# STM32_Temperature_Control.net
KiCad netlist of a schematic drawn in EasyEDA Pro
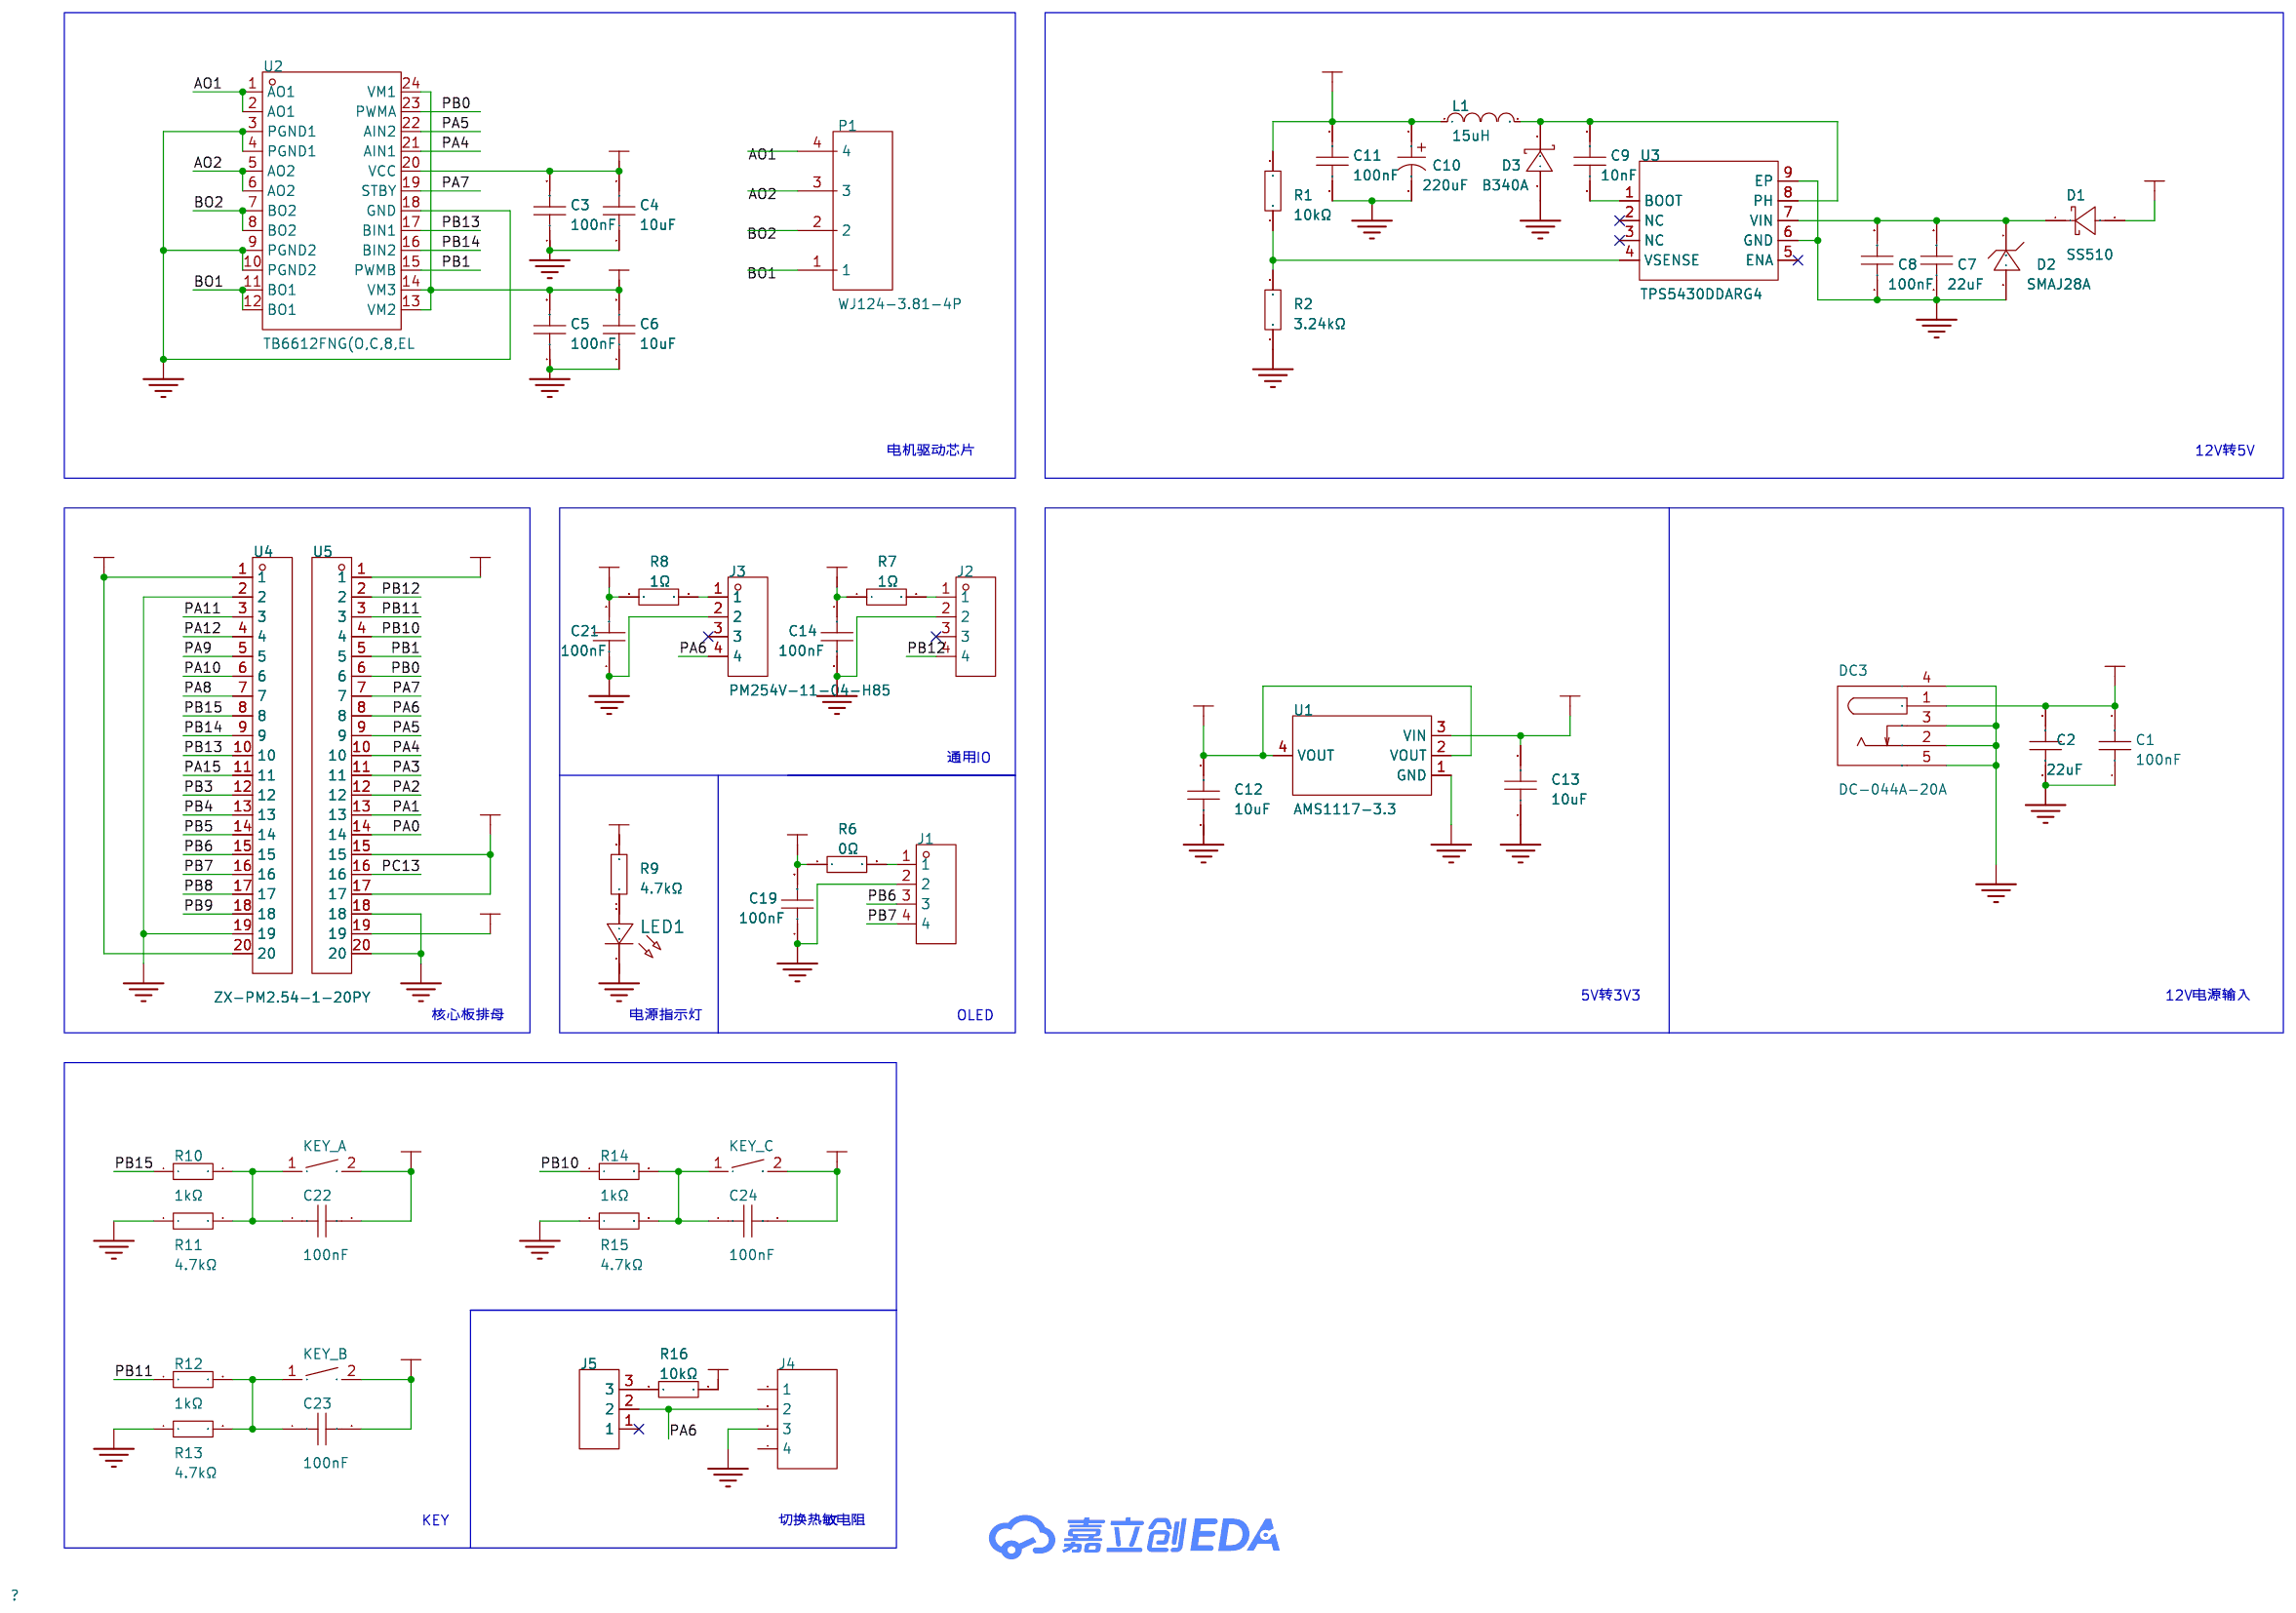
[diagram p0: schematic sheet]

(export (version "E")
  (design (tool "Eeschema 10.0.6"))
  (components
    (comp (ref "C1")
      (value "100nF")
      (footprint "easyedapro:C0603")
      (libsource (lib "easyedapro") (part "Capacitance"))
    )
    (comp (ref "C2")
      (value "22uF")
      (footprint "easyedapro:C0603")
      (fields
        (field (name "Manufacturer Part") "CL21A226MAQNNNE")
        (field (name "Manufacturer") "SAMSUNG(三星)")
      )
      (libsource (lib "easyedapro") (part "Capacitance"))
    )
    (comp (ref "C3")
      (value "100nF")
      (footprint "easyedapro:C0603")
      (libsource (lib "easyedapro") (part "Capacitance"))
    )
    (comp (ref "C4")
      (value "10uF")
      (footprint "easyedapro:C0805")
      (description "容值:10uF;精度:±10%;额定电压:50V;温度系数:X5R;")
      (fields
        (field (name "Manufacturer Part") "GRM21BR61H106KE43L")
        (field (name "Manufacturer") "muRata(村田)")
      )
      (libsource (lib "easyedapro") (part "GRM21BR61H106KE43L"))
    )
    (comp (ref "C5")
      (value "100nF")
      (footprint "easyedapro:C0603")
      (libsource (lib "easyedapro") (part "Capacitance"))
    )
    (comp (ref "C6")
      (value "10uF")
      (footprint "easyedapro:C0805")
      (description "容值:10uF;精度:±10%;额定电压:50V;温度系数:X5R;")
      (fields
        (field (name "Manufacturer Part") "GRM21BR61H106KE43L")
        (field (name "Manufacturer") "muRata(村田)")
      )
      (libsource (lib "easyedapro") (part "GRM21BR61H106KE43L"))
    )
    (comp (ref "C7")
      (value "22uF")
      (footprint "easyedapro:C0603")
      (fields
        (field (name "Manufacturer Part") "CL21A226MAQNNNE")
        (field (name "Manufacturer") "SAMSUNG(三星)")
      )
      (libsource (lib "easyedapro") (part "Capacitance"))
    )
    (comp (ref "C8")
      (value "100nF")
      (footprint "easyedapro:C0603")
      (libsource (lib "easyedapro") (part "Capacitance"))
    )
    (comp (ref "C9")
      (value "10nF")
      (footprint "easyedapro:C0603")
      (libsource (lib "easyedapro") (part "Capacitance"))
    )
    (comp (ref "C10")
      (value "220uF")
      (footprint "easyedapro:CAP-TH_BD6.3-P2.50-D0.5-FD")
      (description "容值:220uF;精度:±20%;额定电压:25V;纹波电流:510mA@100kHz;等效串联电阻(ESR):130mΩ@100kHz;")
      (fields (field (name "Manufacturer Part") "ERG25V220M6X11") (field (name "Manufacturer") "JIERR(捷而瑞)"))
      (libsource (lib "easyedapro") (part "ERG25V220M6X11"))
    )
    (comp (ref "C11")
      (value "100nF")
      (footprint "easyedapro:C0603")
      (libsource (lib "easyedapro") (part "Capacitance"))
    )
    (comp (ref "C12")
      (value "10uF")
      (footprint "easyedapro:C0805")
      (description "容值:10uF;精度:±10%;额定电压:50V;温度系数:X5R;")
      (fields
        (field (name "Manufacturer Part") "GRM21BR61H106KE43L")
        (field (name "Manufacturer") "muRata(村田)")
      )
      (libsource (lib "easyedapro") (part "GRM21BR61H106KE43L"))
    )
    (comp (ref "C13")
      (value "10uF")
      (footprint "easyedapro:C0805")
      (description "容值:10uF;精度:±10%;额定电压:50V;温度系数:X5R;")
      (fields
        (field (name "Manufacturer Part") "GRM21BR61H106KE43L")
        (field (name "Manufacturer") "muRata(村田)")
      )
      (libsource (lib "easyedapro") (part "GRM21BR61H106KE43L"))
    )
    (comp (ref "C14")
      (value "100nF")
      (footprint "easyedapro:C0603")
      (libsource (lib "easyedapro") (part "Capacitance"))
    )
    (comp (ref "C19")
      (value "100nF")
      (footprint "easyedapro:C0603")
      (libsource (lib "easyedapro") (part "Capacitance"))
    )
    (comp (ref "C21")
      (value "100nF")
      (footprint "easyedapro:C0603")
      (libsource (lib "easyedapro") (part "Capacitance"))
    )
    (comp (ref "C22")
      (value "100nF")
      (footprint "easyedapro:C0603")
      (libsource (lib "easyedapro") (part "Capacitance"))
    )
    (comp (ref "C23")
      (value "100nF")
      (footprint "easyedapro:C0603")
      (libsource (lib "easyedapro") (part "Capacitance"))
    )
    (comp (ref "C24")
      (value "100nF")
      (footprint "easyedapro:C0603")
      (libsource (lib "easyedapro") (part "Capacitance"))
    )
    (comp (ref "D1")
      (value "SS510")
      (footprint "easyedapro:SMB_L4.3-W3.6-LS5.4-RD")
      (description "二极管配置:独立式;正向压降(Vf):850mV@5A;直流反向耐压(Vr):100V;整流电流:5A;")
      (fields (field (name "Manufacturer") "YFW(佑风微)"))
      (libsource (lib "easyedapro") (part "SS510_C2898359"))
    )
    (comp (ref "D2")
      (value "SMAJ28A")
      (footprint "easyedapro:SMA_L4.4-W2.6-LS5.0-RD")
      (description "极性:单向;反向截止电压(Vrwm):28V;钳位电压:45.4V;峰值脉冲电流(Ipp):8.8A;峰值脉冲功率(Ppp):400W@10/1000us;击穿电压:31.1V;")
      (fields (field (name "Manufacturer") "AnBon(安邦)"))
      (libsource (lib "easyedapro") (part "SMAJ28A_C397697"))
    )
    (comp (ref "D3")
      (value "B340A")
      (footprint "easyedapro:SMA_L4.3-W2.6-LS5.1-RD")
      (description "二极管配置:独立式;正向压降(Vf):550mV@3A;直流反向耐压(Vr):40V;整流电流:3A;")
      (fields (field (name "Manufacturer") "MDD(辰达半导体)"))
      (libsource (lib "easyedapro") (part "B340A"))
    )
    (comp (ref "DC3")
      (value "DC-044A-20A")
      (footprint "easyedapro:DC-IN-TH_DC-044A-20A")
      (description "连接器类型:DC电源插座;安装方式:弯插;触点内径:2mm;触点外径:5.9mm;额定电流:5A;额定电压:30V;工作温度:-20°C~+70°C;")
      (fields (field (name "Manufacturer") "韩国韩荣"))
      (libsource (lib "easyedapro") (part "DC-044A-20A"))
    )
    (comp (ref "J1")
      (value "PM254V-11-04-H85")
      (footprint "easyedapro:HDR-TH_4P-P2.54-V-F")
      (fields (field (name "Manufacturer") "XFCN(兴飞)"))
      (libsource (lib "easyedapro") (part "PM254V-11-04-H85"))
    )
    (comp (ref "J2")
      (value "PM254V-11-04-H85")
      (footprint "easyedapro:HDR-TH_4P-P2.54-V-F")
      (fields (field (name "Manufacturer") "XFCN(兴飞)"))
      (libsource (lib "easyedapro") (part "PM254V-11-04-H85"))
    )
    (comp (ref "J3")
      (value "PM254V-11-04-H85")
      (footprint "easyedapro:HDR-TH_4P-P2.54-V-F")
      (fields (field (name "Manufacturer") "XFCN(兴飞)"))
      (libsource (lib "easyedapro") (part "PM254V-11-04-H85"))
    )
    (comp (ref "J4")
      (value "B-2100S04P-A110")
      (footprint "easyedapro:HDR-TH_4P-P2.54-V-M")
      (fields (field (name "Manufacturer") "Ckmtw(灿科盟)"))
      (libsource (lib "easyedapro") (part "Header-Male-2.54_1x4"))
    )
    (comp (ref "J5")
      (value "PZ254V-11-03P")
      (footprint "easyedapro:HDR-TH_3P-P2.54-V-M")
      (fields (field (name "Manufacturer") "XFCN(兴飞)"))
      (libsource (lib "easyedapro") (part "PZ254V-11-03P_C2937625"))
    )
    (comp (ref "KEY_A")
      (value "HX 3x4x2-2P-1.6N TACTILE SWITCH")
      (footprint "easyedapro:KEY-SMD_L4.0-W3.0-LS4.9-1")
      (fields (field (name "Manufacturer") "hanxia(韩下)"))
      (libsource (lib "easyedapro") (part "HX 3X4X2-2P-1.6N TACTILE SWITCH"))
    )
    (comp (ref "KEY_B")
      (value "HX 3x4x2-2P-1.6N TACTILE SWITCH")
      (footprint "easyedapro:KEY-SMD_L4.0-W3.0-LS4.9-1")
      (fields (field (name "Manufacturer") "hanxia(韩下)"))
      (libsource (lib "easyedapro") (part "HX 3X4X2-2P-1.6N TACTILE SWITCH"))
    )
    (comp (ref "KEY_C")
      (value "HX 3x4x2-2P-1.6N TACTILE SWITCH")
      (footprint "easyedapro:KEY-SMD_L4.0-W3.0-LS4.9-1")
      (fields (field (name "Manufacturer") "hanxia(韩下)"))
      (libsource (lib "easyedapro") (part "HX 3X4X2-2P-1.6N TACTILE SWITCH"))
    )
    (comp (ref "L1")
      (value "15uH")
      (footprint "easyedapro:IND-SMD_L7.0-W6.6_FXL0630")
      (description "电感值:15uH;精度:±20%;额定电流:3A;饱和电流(Isat):4A;类型:一体成型电感;")
      (fields (field (name "Manufacturer Part") "FXL0630-150-M") (field (name "Manufacturer") "cjiang(长江微电)"))
      (libsource (lib "easyedapro") (part "FXL0630-150-M"))
    )
    (comp (ref "LED1")
      (value "LS R976-NR-1-0-20-R18")
      (footprint "easyedapro:LED_0805")
      (libsource (lib "easyedapro") (part "LED_R"))
    )
    (comp (ref "P1")
      (value "WJ124-3.81-4P")
      (footprint "easyedapro:CONN-TH_4P-P3.81_KF124-3.81-4P")
      (fields (field (name "Manufacturer") "KANGNEX(康奈克斯电气)"))
      (libsource (lib "easyedapro") (part "WJ124-3.81-4P"))
    )
    (comp (ref "R1") (value "10kΩ") (footprint "easyedapro:R0805") (libsource (lib "easyedapro") (part "电阻")))
    (comp (ref "R2")
      (value "3.24kΩ")
      (footprint "easyedapro:R0805")
      (libsource (lib "easyedapro") (part "电阻"))
    )
    (comp (ref "R6") (value "0Ω") (footprint "easyedapro:R0805") (libsource (lib "easyedapro") (part "电阻")))
    (comp (ref "R7") (value "1Ω") (footprint "easyedapro:R0805") (libsource (lib "easyedapro") (part "电阻")))
    (comp (ref "R8") (value "1Ω") (footprint "easyedapro:R0805") (libsource (lib "easyedapro") (part "电阻")))
    (comp (ref "R9")
      (value "4.7kΩ")
      (footprint "easyedapro:R0805")
      (libsource (lib "easyedapro") (part "电阻"))
    )
    (comp (ref "R10") (value "1kΩ") (footprint "easyedapro:R0805") (libsource (lib "easyedapro") (part "电阻")))
    (comp (ref "R11")
      (value "4.7kΩ")
      (footprint "easyedapro:R0805")
      (libsource (lib "easyedapro") (part "电阻"))
    )
    (comp (ref "R12") (value "1kΩ") (footprint "easyedapro:R0805") (libsource (lib "easyedapro") (part "电阻")))
    (comp (ref "R13")
      (value "4.7kΩ")
      (footprint "easyedapro:R0805")
      (libsource (lib "easyedapro") (part "电阻"))
    )
    (comp (ref "R14") (value "1kΩ") (footprint "easyedapro:R0805") (libsource (lib "easyedapro") (part "电阻")))
    (comp (ref "R15")
      (value "4.7kΩ")
      (footprint "easyedapro:R0805")
      (libsource (lib "easyedapro") (part "电阻"))
    )
    (comp (ref "R16")
      (value "10kΩ")
      (footprint "easyedapro:R0805")
      (libsource (lib "easyedapro") (part "电阻"))
    )
    (comp (ref "U1")
      (value "AMS1117-3.3")
      (footprint "easyedapro:SOT-223-3_L6.5-W3.4-P2.30-LS7.0-BR")
      (description "输出类型:固定;工作电压:16V;输出电压:3.3V;输出电流:1A;电源纹波抑制比(PSRR):72dB@(120Hz);输出极性:正极;")
      (fields (field (name "Manufacturer") "AMS"))
      (libsource (lib "easyedapro") (part "AMS1117-3.3"))
    )
    (comp (ref "U2")
      (value "TB6612FNG(O,C,8,EL")
      (footprint "easyedapro:SSOP-24_L8.4-W5.8-P0.65-LS7.8-BL")
      (description "双直流电机驱动器集成电路")
      (fields (field (name "Manufacturer") "TOSHIBA(东芝)"))
      (libsource (lib "easyedapro") (part "TB6612FNG(O,C,8,EL"))
    )
    (comp (ref "U3")
      (value "TPS5430DDARG4")
      (footprint "easyedapro:SO-8_L4.9-W3.9-P1.27-LS6.0-BL-EP")
      (description "功能类型:降压型;工作电压:5.5V~36V;输出电压:1.221V~32.04V;输出电流:3A;输出类型:可调;")
      (fields (field (name "Manufacturer") "TI(德州仪器)"))
      (libsource (lib "easyedapro") (part "TPS5430DDARG4"))
    )
    (comp (ref "U4")
      (value "ZX-PM2.54-1-20PY")
      (footprint "easyedapro:HDR-TH_20P-P2.54-V-F")
      (fields (field (name "Manufacturer") "Megastar(兆星)"))
      (libsource (lib "easyedapro") (part "ZX-PM2.54-1-20PY"))
    )
    (comp (ref "U5")
      (value "ZX-PM2.54-1-20PY")
      (footprint "easyedapro:HDR-TH_20P-P2.54-V-F")
      (fields (field (name "Manufacturer") "Megastar(兆星)"))
      (libsource (lib "easyedapro") (part "ZX-PM2.54-1-20PY"))
    )
  )
  (nets
    (net (code "1") (name "/AO1") (class "Default")
      (node (ref "P1") (pin "4") (pinfunction "4_4") (pintype "input"))
      (node (ref "U2") (pin "1") (pinfunction "AO1_1") (pintype "unspecified"))
      (node (ref "U2") (pin "2") (pinfunction "AO1_2") (pintype "unspecified"))
    )
    (net (code "2") (name "/AO2") (class "Default")
      (node (ref "P1") (pin "3") (pinfunction "3_3") (pintype "input"))
      (node (ref "U2") (pin "5") (pinfunction "AO2_5") (pintype "unspecified"))
      (node (ref "U2") (pin "6") (pinfunction "AO2_6") (pintype "unspecified"))
    )
    (net (code "3") (name "/BO1") (class "Default")
      (node (ref "P1") (pin "1") (pinfunction "1_1") (pintype "input"))
      (node (ref "U2") (pin "11") (pinfunction "BO1_11") (pintype "unspecified"))
      (node (ref "U2") (pin "12") (pinfunction "BO1_12") (pintype "unspecified"))
    )
    (net (code "4") (name "/BO2") (class "Default")
      (node (ref "P1") (pin "2") (pinfunction "2_2") (pintype "input"))
      (node (ref "U2") (pin "7") (pinfunction "BO2_7") (pintype "unspecified"))
      (node (ref "U2") (pin "8") (pinfunction "BO2_8") (pintype "unspecified"))
    )
    (net (code "5") (name "/PA0") (class "Default")
      (node (ref "U5") (pin "14") (pinfunction "14_14") (pintype "unspecified"))
    )
    (net (code "6") (name "/PA1") (class "Default")
      (node (ref "U5") (pin "13") (pinfunction "13_13") (pintype "unspecified"))
    )
    (net (code "7") (name "/PA2") (class "Default")
      (node (ref "U5") (pin "12") (pinfunction "12_12") (pintype "unspecified"))
    )
    (net (code "8") (name "/PA3") (class "Default")
      (node (ref "U5") (pin "11") (pinfunction "11_11") (pintype "unspecified"))
    )
    (net (code "9") (name "/PA4") (class "Default")
      (node (ref "U2") (pin "21") (pinfunction "AIN1_21") (pintype "unspecified"))
      (node (ref "U5") (pin "10") (pinfunction "10_10") (pintype "unspecified"))
    )
    (net (code "10") (name "/PA5") (class "Default")
      (node (ref "U2") (pin "22") (pinfunction "AIN2_22") (pintype "unspecified"))
      (node (ref "U5") (pin "9") (pinfunction "9_9") (pintype "unspecified"))
    )
    (net (code "11") (name "/PA6") (class "Default")
      (node (ref "J3") (pin "4") (pinfunction "4_4") (pintype "unspecified"))
      (node (ref "J4") (pin "2") (pinfunction "2_2") (pintype "unspecified"))
      (node (ref "J5") (pin "2") (pinfunction "2_2") (pintype "unspecified"))
      (node (ref "U5") (pin "8") (pinfunction "8_8") (pintype "unspecified"))
    )
    (net (code "12") (name "/PA7") (class "Default")
      (node (ref "U2") (pin "19") (pinfunction "STBY_19") (pintype "unspecified"))
      (node (ref "U5") (pin "7") (pinfunction "7_7") (pintype "unspecified"))
    )
    (net (code "13") (name "/PA8") (class "Default")
      (node (ref "U4") (pin "7") (pinfunction "7_7") (pintype "unspecified"))
    )
    (net (code "14") (name "/PA9") (class "Default")
      (node (ref "U4") (pin "5") (pinfunction "5_5") (pintype "unspecified"))
    )
    (net (code "15") (name "/PA10") (class "Default")
      (node (ref "U4") (pin "6") (pinfunction "6_6") (pintype "unspecified"))
    )
    (net (code "16") (name "/PA11") (class "Default")
      (node (ref "U4") (pin "3") (pinfunction "3_3") (pintype "unspecified"))
    )
    (net (code "17") (name "/PA12") (class "Default")
      (node (ref "U4") (pin "4") (pinfunction "4_4") (pintype "unspecified"))
    )
    (net (code "18") (name "/PA15") (class "Default")
      (node (ref "U4") (pin "11") (pinfunction "11_11") (pintype "unspecified"))
    )
    (net (code "19") (name "/PB0") (class "Default")
      (node (ref "U2") (pin "23") (pinfunction "PWMA_23") (pintype "unspecified"))
      (node (ref "U5") (pin "6") (pinfunction "6_6") (pintype "unspecified"))
    )
    (net (code "20") (name "/PB1") (class "Default")
      (node (ref "U2") (pin "15") (pinfunction "PWMB_15") (pintype "unspecified"))
      (node (ref "U5") (pin "5") (pinfunction "5_5") (pintype "unspecified"))
    )
    (net (code "21") (name "/PB3") (class "Default")
      (node (ref "U4") (pin "12") (pinfunction "12_12") (pintype "unspecified"))
    )
    (net (code "22") (name "/PB4") (class "Default")
      (node (ref "U4") (pin "13") (pinfunction "13_13") (pintype "unspecified"))
    )
    (net (code "23") (name "/PB5") (class "Default")
      (node (ref "U4") (pin "14") (pinfunction "14_14") (pintype "unspecified"))
    )
    (net (code "24") (name "/PB6") (class "Default")
      (node (ref "J1") (pin "3") (pinfunction "3_3") (pintype "unspecified"))
      (node (ref "U4") (pin "15") (pinfunction "15_15") (pintype "unspecified"))
    )
    (net (code "25") (name "/PB7") (class "Default")
      (node (ref "J1") (pin "4") (pinfunction "4_4") (pintype "unspecified"))
      (node (ref "U4") (pin "16") (pinfunction "16_16") (pintype "unspecified"))
    )
    (net (code "26") (name "/PB8") (class "Default")
      (node (ref "U4") (pin "17") (pinfunction "17_17") (pintype "unspecified"))
    )
    (net (code "27") (name "/PB9") (class "Default")
      (node (ref "U4") (pin "18") (pinfunction "18_18") (pintype "unspecified"))
    )
    (net (code "28") (name "/PB10") (class "Default")
      (node (ref "R14") (pin "1") (pinfunction "1_1") (pintype "input"))
      (node (ref "U5") (pin "4") (pinfunction "4_4") (pintype "unspecified"))
    )
    (net (code "29") (name "/PB11") (class "Default")
      (node (ref "R12") (pin "1") (pinfunction "1_1") (pintype "input"))
      (node (ref "U5") (pin "3") (pinfunction "3_3") (pintype "unspecified"))
    )
    (net (code "30") (name "/PB12") (class "Default")
      (node (ref "J2") (pin "4") (pinfunction "4_4") (pintype "unspecified"))
      (node (ref "U5") (pin "2") (pinfunction "2_2") (pintype "unspecified"))
    )
    (net (code "31") (name "/PB13") (class "Default")
      (node (ref "U2") (pin "17") (pinfunction "BIN1_17") (pintype "unspecified"))
      (node (ref "U4") (pin "10") (pinfunction "10_10") (pintype "unspecified"))
    )
    (net (code "32") (name "/PB14") (class "Default")
      (node (ref "U2") (pin "16") (pinfunction "BIN2_16") (pintype "unspecified"))
      (node (ref "U4") (pin "9") (pinfunction "9_9") (pintype "unspecified"))
    )
    (net (code "33") (name "/PB15") (class "Default")
      (node (ref "R10") (pin "1") (pinfunction "1_1") (pintype "input"))
      (node (ref "U4") (pin "8") (pinfunction "8_8") (pintype "unspecified"))
    )
    (net (code "34") (name "/PC13") (class "Default")
      (node (ref "U5") (pin "16") (pinfunction "16_16") (pintype "unspecified"))
    )
    (net (code "35") (name "3V3") (class "Default")
      (node (ref "C12") (pin "2") (pinfunction "2_2") (pintype "unspecified"))
      (node (ref "C14") (pin "1") (pinfunction "1_1") (pintype "input"))
      (node (ref "C19") (pin "2") (pinfunction "2_2") (pintype "input"))
      (node (ref "C21") (pin "2") (pinfunction "2_2") (pintype "input"))
      (node (ref "C22") (pin "2") (pinfunction "2_2") (pintype "input"))
      (node (ref "C23") (pin "2") (pinfunction "2_2") (pintype "input"))
      (node (ref "C24") (pin "2") (pinfunction "2_2") (pintype "input"))
      (node (ref "C3") (pin "2") (pinfunction "2_2") (pintype "input"))
      (node (ref "C4") (pin "2") (pinfunction "2_2") (pintype "unspecified"))
      (node (ref "KEY_A") (pin "2") (pinfunction "2_2") (pintype "unspecified"))
      (node (ref "KEY_B") (pin "2") (pinfunction "2_2") (pintype "unspecified"))
      (node (ref "KEY_C") (pin "2") (pinfunction "2_2") (pintype "unspecified"))
      (node (ref "R16") (pin "1") (pinfunction "1_1") (pintype "input"))
      (node (ref "R6") (pin "1") (pinfunction "1_1") (pintype "input"))
      (node (ref "R7") (pin "1") (pinfunction "1_1") (pintype "input"))
      (node (ref "R8") (pin "1") (pinfunction "1_1") (pintype "input"))
      (node (ref "R9") (pin "2") (pinfunction "2_2") (pintype "input"))
      (node (ref "U1") (pin "2") (pinfunction "VOUT_2") (pintype "unspecified"))
      (node (ref "U1") (pin "4") (pinfunction "VOUT_4") (pintype "unspecified"))
      (node (ref "U2") (pin "20") (pinfunction "VCC_20") (pintype "unspecified"))
      (node (ref "U4") (pin "1") (pinfunction "1_1") (pintype "unspecified"))
      (node (ref "U4") (pin "20") (pinfunction "20_20") (pintype "unspecified"))
      (node (ref "U5") (pin "1") (pinfunction "1_1") (pintype "unspecified"))
      (node (ref "U5") (pin "15") (pinfunction "15_15") (pintype "unspecified"))
      (node (ref "U5") (pin "17") (pinfunction "17_17") (pintype "unspecified"))
    )
    (net (code "36") (name "5V") (class "Default")
      (node (ref "C10") (pin "1") (pinfunction "1_1") (pintype "input"))
      (node (ref "C11") (pin "1") (pinfunction "1_1") (pintype "input"))
      (node (ref "C13") (pin "2") (pinfunction "2_2") (pintype "unspecified"))
      (node (ref "C5") (pin "2") (pinfunction "2_2") (pintype "input"))
      (node (ref "C6") (pin "2") (pinfunction "2_2") (pintype "unspecified"))
      (node (ref "L1") (pin "1") (pinfunction "1_1") (pintype "unspecified"))
      (node (ref "R1") (pin "2") (pinfunction "2_2") (pintype "input"))
      (node (ref "U1") (pin "3") (pinfunction "VIN_3") (pintype "unspecified"))
      (node (ref "U2") (pin "13") (pinfunction "VM2_13") (pintype "unspecified"))
      (node (ref "U2") (pin "14") (pinfunction "VM3_14") (pintype "unspecified"))
      (node (ref "U2") (pin "24") (pinfunction "VM1_24") (pintype "unspecified"))
    )
    (net (code "37") (name "5V_USB") (class "Default")
      (node (ref "U5") (pin "19") (pinfunction "19_19") (pintype "unspecified"))
    )
    (net (code "38") (name "12V") (class "Default")
      (node (ref "C1") (pin "2") (pinfunction "2_2") (pintype "input"))
      (node (ref "C2") (pin "2") (pinfunction "2_2") (pintype "input"))
      (node (ref "D1") (pin "2") (pinfunction "A_2") (pintype "unspecified"))
      (node (ref "DC3") (pin "1") (pinfunction "1_1") (pintype "unspecified"))
    )
    (net (code "39") (name "GND") (class "Default")
      (node (ref "C1") (pin "1") (pinfunction "1_1") (pintype "input"))
      (node (ref "C10") (pin "2") (pinfunction "2_2") (pintype "input"))
      (node (ref "C11") (pin "2") (pinfunction "2_2") (pintype "input"))
      (node (ref "C12") (pin "1") (pinfunction "1_1") (pintype "unspecified"))
      (node (ref "C13") (pin "1") (pinfunction "1_1") (pintype "unspecified"))
      (node (ref "C14") (pin "2") (pinfunction "2_2") (pintype "input"))
      (node (ref "C19") (pin "1") (pinfunction "1_1") (pintype "input"))
      (node (ref "C2") (pin "1") (pinfunction "1_1") (pintype "input"))
      (node (ref "C21") (pin "1") (pinfunction "1_1") (pintype "input"))
      (node (ref "C3") (pin "1") (pinfunction "1_1") (pintype "input"))
      (node (ref "C4") (pin "1") (pinfunction "1_1") (pintype "unspecified"))
      (node (ref "C5") (pin "1") (pinfunction "1_1") (pintype "input"))
      (node (ref "C6") (pin "1") (pinfunction "1_1") (pintype "unspecified"))
      (node (ref "C7") (pin "1") (pinfunction "1_1") (pintype "input"))
      (node (ref "C8") (pin "1") (pinfunction "1_1") (pintype "input"))
      (node (ref "D2") (pin "2") (pinfunction "A_2") (pintype "unspecified"))
      (node (ref "D3") (pin "2") (pinfunction "A_2") (pintype "unspecified"))
      (node (ref "DC3") (pin "2") (pinfunction "2_2") (pintype "unspecified"))
      (node (ref "DC3") (pin "3") (pinfunction "3_3") (pintype "unspecified"))
      (node (ref "DC3") (pin "4") (pinfunction "4_4") (pintype "unspecified"))
      (node (ref "DC3") (pin "5") (pinfunction "5_5") (pintype "unspecified"))
      (node (ref "J1") (pin "2") (pinfunction "2_2") (pintype "unspecified"))
      (node (ref "J2") (pin "2") (pinfunction "2_2") (pintype "unspecified"))
      (node (ref "J3") (pin "2") (pinfunction "2_2") (pintype "unspecified"))
      (node (ref "J4") (pin "3") (pinfunction "3_3") (pintype "unspecified"))
      (node (ref "LED1") (pin "1") (pinfunction "C_1") (pintype "input"))
      (node (ref "R11") (pin "1") (pinfunction "1_1") (pintype "input"))
      (node (ref "R13") (pin "1") (pinfunction "1_1") (pintype "input"))
      (node (ref "R15") (pin "1") (pinfunction "1_1") (pintype "input"))
      (node (ref "R2") (pin "1") (pinfunction "1_1") (pintype "input"))
      (node (ref "U1") (pin "1") (pinfunction "GND_1") (pintype "unspecified"))
      (node (ref "U2") (pin "10") (pinfunction "PGND2_10") (pintype "unspecified"))
      (node (ref "U2") (pin "18") (pinfunction "GND_18") (pintype "unspecified"))
      (node (ref "U2") (pin "3") (pinfunction "PGND1_3") (pintype "unspecified"))
      (node (ref "U2") (pin "4") (pinfunction "PGND1_4") (pintype "unspecified"))
      (node (ref "U2") (pin "9") (pinfunction "PGND2_9") (pintype "unspecified"))
      (node (ref "U3") (pin "6") (pinfunction "GND_6") (pintype "unspecified"))
      (node (ref "U3") (pin "9") (pinfunction "EP_9") (pintype "unspecified"))
      (node (ref "U4") (pin "19") (pinfunction "19_19") (pintype "unspecified"))
      (node (ref "U4") (pin "2") (pinfunction "2_2") (pintype "unspecified"))
      (node (ref "U5") (pin "18") (pinfunction "18_18") (pintype "unspecified"))
      (node (ref "U5") (pin "20") (pinfunction "20_20") (pintype "unspecified"))
    )
    (net (code "40") (name "Net-(C22-Pad1)") (class "Default")
      (node (ref "C22") (pin "1") (pinfunction "1_1") (pintype "input"))
      (node (ref "KEY_A") (pin "1") (pinfunction "1_1") (pintype "unspecified"))
      (node (ref "R10") (pin "2") (pinfunction "2_2") (pintype "input"))
      (node (ref "R11") (pin "2") (pinfunction "2_2") (pintype "input"))
    )
    (net (code "41") (name "Net-(C23-Pad1)") (class "Default")
      (node (ref "C23") (pin "1") (pinfunction "1_1") (pintype "input"))
      (node (ref "KEY_B") (pin "1") (pinfunction "1_1") (pintype "unspecified"))
      (node (ref "R12") (pin "2") (pinfunction "2_2") (pintype "input"))
      (node (ref "R13") (pin "2") (pinfunction "2_2") (pintype "input"))
    )
    (net (code "42") (name "Net-(C24-Pad1)") (class "Default")
      (node (ref "C24") (pin "1") (pinfunction "1_1") (pintype "input"))
      (node (ref "KEY_C") (pin "1") (pinfunction "1_1") (pintype "unspecified"))
      (node (ref "R14") (pin "2") (pinfunction "2_2") (pintype "input"))
      (node (ref "R15") (pin "2") (pinfunction "2_2") (pintype "input"))
    )
    (net (code "43") (name "Net-(D1-K)") (class "Default")
      (node (ref "C7") (pin "2") (pinfunction "2_2") (pintype "input"))
      (node (ref "C8") (pin "2") (pinfunction "2_2") (pintype "input"))
      (node (ref "D1") (pin "1") (pinfunction "K_1") (pintype "unspecified"))
      (node (ref "D2") (pin "1") (pinfunction "C_1") (pintype "unspecified"))
      (node (ref "U3") (pin "7") (pinfunction "VIN_7") (pintype "unspecified"))
    )
    (net (code "44") (name "Net-(D3-K)") (class "Default")
      (node (ref "C9") (pin "2") (pinfunction "2_2") (pintype "input"))
      (node (ref "D3") (pin "1") (pinfunction "K_1") (pintype "unspecified"))
      (node (ref "L1") (pin "2") (pinfunction "2_2") (pintype "unspecified"))
      (node (ref "U3") (pin "8") (pinfunction "PH_8") (pintype "unspecified"))
    )
    (net (code "45") (name "Net-(J1-Pad1)") (class "Default")
      (node (ref "J1") (pin "1") (pinfunction "1_1") (pintype "unspecified"))
      (node (ref "R6") (pin "2") (pinfunction "2_2") (pintype "input"))
    )
    (net (code "46") (name "Net-(J2-Pad1)") (class "Default")
      (node (ref "J2") (pin "1") (pinfunction "1_1") (pintype "unspecified"))
      (node (ref "R7") (pin "2") (pinfunction "2_2") (pintype "input"))
    )
    (net (code "47") (name "Net-(J3-Pad1)") (class "Default")
      (node (ref "J3") (pin "1") (pinfunction "1_1") (pintype "unspecified"))
      (node (ref "R8") (pin "2") (pinfunction "2_2") (pintype "input"))
    )
    (net (code "48") (name "Net-(J5-Pad3)") (class "Default")
      (node (ref "J5") (pin "3") (pinfunction "3_3") (pintype "unspecified"))
      (node (ref "R16") (pin "2") (pinfunction "2_2") (pintype "input"))
    )
    (net (code "49") (name "Net-(LED1-A)") (class "Default")
      (node (ref "LED1") (pin "2") (pinfunction "A_2") (pintype "input"))
      (node (ref "R9") (pin "1") (pinfunction "1_1") (pintype "input"))
    )
    (net (code "50") (name "Net-(U3-BOOT)") (class "Default")
      (node (ref "C9") (pin "1") (pinfunction "1_1") (pintype "input"))
      (node (ref "U3") (pin "1") (pinfunction "BOOT_1") (pintype "unspecified"))
    )
    (net (code "51") (name "Net-(U3-VSENSE)") (class "Default")
      (node (ref "R1") (pin "1") (pinfunction "1_1") (pintype "input"))
      (node (ref "R2") (pin "2") (pinfunction "2_2") (pintype "input"))
      (node (ref "U3") (pin "4") (pinfunction "VSENSE_4") (pintype "unspecified"))
    )
    (net (code "52") (name "unconnected-(J2-Pad3)") (class "Default")
      (node (ref "J2") (pin "3") (pinfunction "3_3") (pintype "unspecified+no_connect"))
    )
    (net (code "53") (name "unconnected-(J3-Pad3)") (class "Default")
      (node (ref "J3") (pin "3") (pinfunction "3_3") (pintype "unspecified+no_connect"))
    )
    (net (code "54") (name "unconnected-(J4-Pad1)") (class "Default")
      (node (ref "J4") (pin "1") (pinfunction "1_1") (pintype "unspecified"))
    )
    (net (code "55") (name "unconnected-(J4-Pad4)") (class "Default")
      (node (ref "J4") (pin "4") (pinfunction "4_4") (pintype "unspecified"))
    )
    (net (code "56") (name "unconnected-(J5-Pad1)") (class "Default")
      (node (ref "J5") (pin "1") (pinfunction "1_1") (pintype "unspecified+no_connect"))
    )
    (net (code "57") (name "unconnected-(U3-ENA-Pad5)") (class "Default")
      (node (ref "U3") (pin "5") (pinfunction "ENA_5") (pintype "unspecified+no_connect"))
    )
    (net (code "58") (name "unconnected-(U3-NC-Pad2)") (class "Default")
      (node (ref "U3") (pin "2") (pinfunction "NC_2") (pintype "unspecified+no_connect"))
    )
    (net (code "59") (name "unconnected-(U3-NC-Pad3)") (class "Default")
      (node (ref "U3") (pin "3") (pinfunction "NC_3") (pintype "unspecified+no_connect"))
    )
  )
)
